# IO.net
KiCad netlist of a schematic drawn in Altium Designer
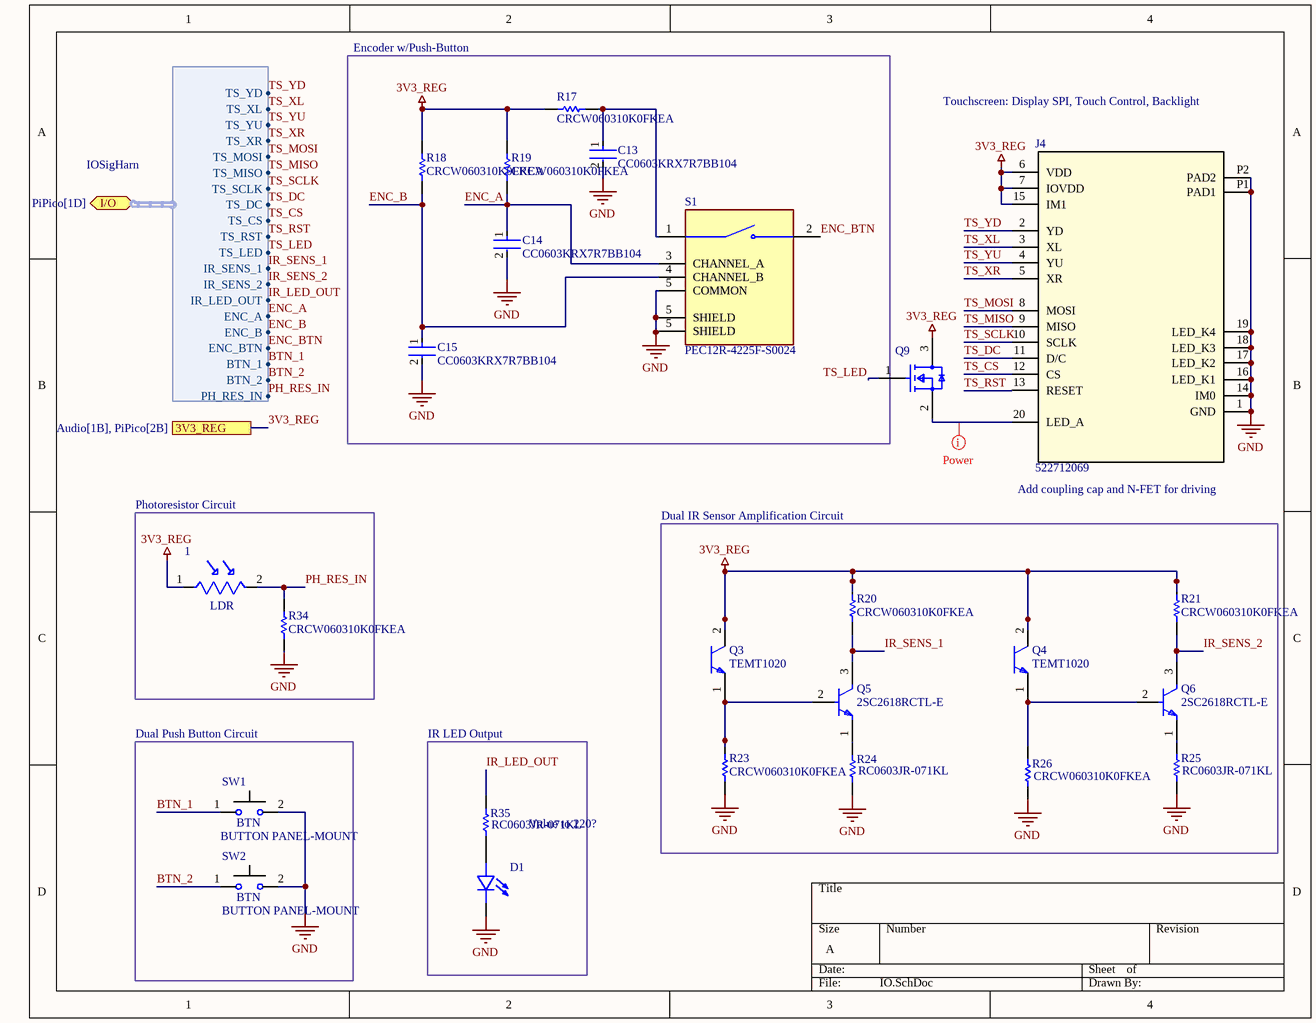
[diagram p0: IO.SchDoc]

(export (version "E")
  (design (tool "Eeschema 10.0.6"))
  (components
    (comp (ref "1")
      (value "LDR")
      (footprint "2-pin Header (Generic)")
      (description "Generic Photoresistor symbol for peripheral use.\r\nUses generic 2-Pin Header footprint.")
      (libsource (lib "ECE299_PCB") (part "PHOTORESISTOR GENERIC"))
    )
    (comp (ref "C13")
      (value "CC0603KRX7R7BB104")
      (footprint "FP-CC0603-DA-MFG")
      (description "CAP CER 0.1UF 16V X7R 0603")
      (fields
        (field (name "OCTOPART") "https://octopart.com/cc0603krx7r7bb104-yageo-192941")
        (field (name "TOLERANCE") "0.1")
      )
      (libsource (lib "Altium Content Vault") (part "11868f565c42a9108669ba33697ecf6"))
    )
    (comp (ref "C14")
      (value "CC0603KRX7R7BB104")
      (footprint "FP-CC0603-DA-MFG")
      (description "CAP CER 0.1UF 16V X7R 0603")
      (fields
        (field (name "OCTOPART") "https://octopart.com/cc0603krx7r7bb104-yageo-192941")
        (field (name "TOLERANCE") "0.1")
      )
      (libsource (lib "Altium Content Vault") (part "11868f565c42a9108669ba33697ecf6"))
    )
    (comp (ref "C15")
      (value "CC0603KRX7R7BB104")
      (footprint "FP-CC0603-DA-MFG")
      (description "CAP CER 0.1UF 16V X7R 0603")
      (fields
        (field (name "OCTOPART") "https://octopart.com/cc0603krx7r7bb104-yageo-192941")
        (field (name "TOLERANCE") "0.1")
      )
      (libsource (lib "Altium Content Vault") (part "11868f565c42a9108669ba33697ecf6"))
    )
    (comp (ref "D1")
      (value "~")
      (footprint "2-pin Header (Generic)")
      (description "IR_LED")
      (fields (field (name "MF") "{'manufacturer': u'Kingbright'}") (field (name "MP") "APT1608SF4C-PRV"))
      (libsource (lib "APT1608SF4C-PRV") (part "APT1608SF4C-PRV"))
    )
    (comp (ref "J4")
      (value "522712069")
      (footprint "CON_522712069_MOL")
      (libsource (lib "522712069") (part "522712069"))
    )
    (comp (ref "Q3")
      (value "TEMT1020")
      (footprint "FP-6_544-5325_01-4-MFG")
      (description "SENSOR PHOTO 880NM TOP VIEW 2SMD")
      (fields
        (field (name "OCTOPART") "https://octopart.com/temt1020-vishay-39666707")
        (field (name "MANUFACTURER") "Vishay Semiconductor Opto Division")
      )
      (libsource (lib "Altium Content Vault") (part "dcd88daa71cb945d3e90ade5296eb2f"))
    )
    (comp (ref "Q4")
      (value "TEMT1020")
      (footprint "FP-6_544-5325_01-4-MFG")
      (description "SENSOR PHOTO 880NM TOP VIEW 2SMD")
      (fields
        (field (name "OCTOPART") "https://octopart.com/temt1020-vishay-39666707")
        (field (name "MANUFACTURER") "Vishay Semiconductor Opto Division")
      )
      (libsource (lib "Altium Content Vault") (part "dcd88daa71cb945d3e90ade5296eb2f"))
    )
    (comp (ref "Q5")
      (value "2SC2618RCTL-E")
      (footprint "PLSP0003ZB-A_P213_MFG")
      (description "Trans Gp Bjt NPN 35V 0.5A 3-PIN Mpak T/r")
      (libsource (lib "Altium Content Vault") (part "66ef7c62b17c908413b088e63760a96"))
    )
    (comp (ref "Q6")
      (value "2SC2618RCTL-E")
      (footprint "PLSP0003ZB-A_P213_MFG")
      (description "Trans Gp Bjt NPN 35V 0.5A 3-PIN Mpak T/r")
      (libsource (lib "Altium Content Vault") (part "66ef7c62b17c908413b088e63760a96"))
    )
    (comp (ref "Q9")
      (value "2N7002H6327XTSA2")
      (footprint "FP-PG-SOT23-3-MFG")
      (description "MOSFET N-CH 60V 0.3A SOT23")
      (libsource (lib "Altium Content Vault") (part "2d979dc9c009d20783d0745ce0ba7b4"))
    )
    (comp (ref "R17")
      (value "CRCW060310K0FKEA")
      (footprint "RESC1609X50X30NL8T20")
      (description "Chip Resistor, 10 KOhm, +/- 1%, 100 mW, -55 to 155 degC, 0603 (1608 Metric), RoHS, Tape and Reel")
      (fields (field (name "MANUFACTURER") "Vishay Semiconductor"))
      (libsource (lib "Altium Content Vault") (part "RES-2"))
    )
    (comp (ref "R18")
      (value "CRCW060310K0FKEA")
      (footprint "RESC1609X50X30NL8T20")
      (description "Chip Resistor, 10 KOhm, +/- 1%, 100 mW, -55 to 155 degC, 0603 (1608 Metric), RoHS, Tape and Reel")
      (fields (field (name "MANUFACTURER") "Vishay Semiconductor"))
      (libsource (lib "Altium Content Vault") (part "RES-2"))
    )
    (comp (ref "R19")
      (value "CRCW060310K0FKEA")
      (footprint "RESC1609X50X30NL8T20")
      (description "Chip Resistor, 10 KOhm, +/- 1%, 100 mW, -55 to 155 degC, 0603 (1608 Metric), RoHS, Tape and Reel")
      (fields (field (name "MANUFACTURER") "Vishay Semiconductor"))
      (libsource (lib "Altium Content Vault") (part "RES-2"))
    )
    (comp (ref "R20")
      (value "CRCW060310K0FKEA")
      (footprint "RESC1609X50X30NL8T20")
      (description "Chip Resistor, 10 KOhm, +/- 1%, 100 mW, -55 to 155 degC, 0603 (1608 Metric), RoHS, Tape and Reel")
      (fields (field (name "MANUFACTURER") "Vishay Semiconductor"))
      (libsource (lib "Altium Content Vault") (part "RES-2"))
    )
    (comp (ref "R21")
      (value "CRCW060310K0FKEA")
      (footprint "RESC1609X50X30NL8T20")
      (description "Chip Resistor, 10 KOhm, +/- 1%, 100 mW, -55 to 155 degC, 0603 (1608 Metric), RoHS, Tape and Reel")
      (fields (field (name "MANUFACTURER") "Vishay Semiconductor"))
      (libsource (lib "Altium Content Vault") (part "RES-2"))
    )
    (comp (ref "R23")
      (value "CRCW060310K0FKEA")
      (footprint "RESC1609X50X30NL8T20")
      (description "Chip Resistor, 10 KOhm, +/- 1%, 100 mW, -55 to 155 degC, 0603 (1608 Metric), RoHS, Tape and Reel")
      (fields (field (name "MANUFACTURER") "Vishay Semiconductor"))
      (libsource (lib "Altium Content Vault") (part "RES-2"))
    )
    (comp (ref "R24")
      (value "RC0603JR-071KL")
      (footprint "RESC1608X55X25ML10T15")
      (description "Chip Resistor, 1 KOhm, +/- 5%, 0.063 W, -55 to 155 degC, 0603 (1608 Metric), RoHS, Tape and Reel")
      (fields (field (name "MANUFACTURER") "Yageo"))
      (libsource (lib "Altium Content Vault") (part "RES-2"))
    )
    (comp (ref "R25")
      (value "RC0603JR-071KL")
      (footprint "RESC1608X55X25ML10T15")
      (description "Chip Resistor, 1 KOhm, +/- 5%, 0.063 W, -55 to 155 degC, 0603 (1608 Metric), RoHS, Tape and Reel")
      (fields (field (name "MANUFACTURER") "Yageo"))
      (libsource (lib "Altium Content Vault") (part "RES-2"))
    )
    (comp (ref "R26")
      (value "CRCW060310K0FKEA")
      (footprint "RESC1609X50X30NL8T20")
      (description "Chip Resistor, 10 KOhm, +/- 1%, 100 mW, -55 to 155 degC, 0603 (1608 Metric), RoHS, Tape and Reel")
      (fields (field (name "MANUFACTURER") "Vishay Semiconductor"))
      (libsource (lib "Altium Content Vault") (part "RES-2"))
    )
    (comp (ref "R34")
      (value "CRCW060310K0FKEA")
      (footprint "RESC1609X50X30NL8T20")
      (description "Chip Resistor, 10 KOhm, +/- 1%, 100 mW, -55 to 155 degC, 0603 (1608 Metric), RoHS, Tape and Reel")
      (fields (field (name "MANUFACTURER") "Vishay Semiconductor"))
      (libsource (lib "Altium Content Vault") (part "RES-2"))
    )
    (comp (ref "R35")
      (value "RC0603JR-071KL")
      (footprint "RESC1608X55X25ML10T15")
      (description "Chip Resistor, 1 KOhm, +/- 5%, 0.063 W, -55 to 155 degC, 0603 (1608 Metric), RoHS, Tape and Reel")
      (fields (field (name "MANUFACTURER") "Yageo"))
      (libsource (lib "Altium Content Vault") (part "RES-2"))
    )
    (comp (ref "S1")
      (value "PEC12R-4225F-S0024")
      (footprint "5-pin Header (Generic)")
      (fields (field (name "MF") "Bourns"))
      (libsource (lib "PEC12R-4225F-S0024") (part "PEC12R-4225F-S0024"))
    )
    (comp (ref "SW1")
      (value "BUTTON PANEL-MOUNT")
      (footprint "2-pin Header (Generic)")
      (libsource (lib "ECE299_PCB") (part "BUTTON PANEL-MOUNT"))
    )
    (comp (ref "SW2")
      (value "BUTTON PANEL-MOUNT")
      (footprint "2-pin Header (Generic)")
      (libsource (lib "ECE299_PCB") (part "BUTTON PANEL-MOUNT"))
    )
  )
  (nets
    (net (code "2") (name "/BTN_1") (class "Default") (node (ref "SW1") (pin "1") (pintype "passive")))
    (net (code "3") (name "/BTN_2") (class "Default") (node (ref "SW2") (pin "1") (pintype "passive")))
    (net (code "4") (name "/ENC_A") (class "Default")
      (node (ref "C14") (pin "1") (pinfunction "1_1") (pintype "passive"))
      (node (ref "R19") (pin "1") (pinfunction "1_1") (pintype "passive"))
      (node (ref "S1") (pin "3") (pinfunction "CHANNEL_A_3") (pintype "passive"))
    )
    (net (code "5") (name "/ENC_B") (class "Default")
      (node (ref "C15") (pin "1") (pinfunction "1_1") (pintype "passive"))
      (node (ref "R18") (pin "1") (pinfunction "1_1") (pintype "passive"))
      (node (ref "S1") (pin "4") (pinfunction "CHANNEL_B_4") (pintype "passive"))
    )
    (net (code "6") (name "/ENC_BTN") (class "Default")
      (node (ref "S1") (pin "2") (pinfunction "2_2") (pintype "passive"))
    )
    (net (code "7") (name "/IR_LED_OUT") (class "Default")
      (node (ref "R35") (pin "2") (pinfunction "2_2") (pintype "passive"))
    )
    (net (code "8") (name "/IR_SENS_1") (class "Default")
      (node (ref "Q5") (pin "3") (pinfunction "COLLECTOR_3") (pintype "passive"))
      (node (ref "R20") (pin "1") (pinfunction "1_1") (pintype "passive"))
    )
    (net (code "9") (name "/IR_SENS_2") (class "Default")
      (node (ref "Q6") (pin "3") (pinfunction "COLLECTOR_3") (pintype "passive"))
      (node (ref "R21") (pin "1") (pinfunction "1_1") (pintype "passive"))
    )
    (net (code "10") (name "/PH_RES_IN") (class "Default")
      (node (ref "1") (pin "2") (pintype "passive"))
      (node (ref "R34") (pin "2") (pinfunction "2_2") (pintype "passive"))
    )
    (net (code "11") (name "/TS_CS") (class "Default")
      (node (ref "J4") (pin "12") (pinfunction "CS_12") (pintype "passive"))
    )
    (net (code "12") (name "/TS_DC") (class "Default")
      (node (ref "J4") (pin "11") (pinfunction "D/C_11") (pintype "passive"))
    )
    (net (code "13") (name "/TS_LED") (class "Default")
      (node (ref "Q9") (pin "1") (pinfunction "gate_1") (pintype "passive"))
    )
    (net (code "14") (name "/TS_MISO") (class "Default")
      (node (ref "J4") (pin "9") (pinfunction "MISO_9") (pintype "passive"))
    )
    (net (code "15") (name "/TS_MOSI") (class "Default")
      (node (ref "J4") (pin "8") (pinfunction "MOSI_8") (pintype "passive"))
    )
    (net (code "16") (name "/TS_RST") (class "Default")
      (node (ref "J4") (pin "13") (pinfunction "RESET_13") (pintype "passive"))
    )
    (net (code "17") (name "/TS_SCLK") (class "Default")
      (node (ref "J4") (pin "10") (pinfunction "SCLK_10") (pintype "passive"))
    )
    (net (code "18") (name "/TS_XL") (class "Default")
      (node (ref "J4") (pin "3") (pinfunction "XL_3") (pintype "passive"))
    )
    (net (code "19") (name "/TS_XR") (class "Default")
      (node (ref "J4") (pin "5") (pinfunction "XR_5") (pintype "passive"))
    )
    (net (code "20") (name "/TS_YD") (class "Default")
      (node (ref "J4") (pin "2") (pinfunction "YD_2") (pintype "passive"))
    )
    (net (code "21") (name "/TS_YU") (class "Default")
      (node (ref "J4") (pin "4") (pinfunction "YU_4") (pintype "passive"))
    )
    (net (code "23") (name "<NO NET>") (class "Default")
      (node (ref "1") (pin "1") (pintype "passive"))
      (node (ref "J4") (pin "15") (pinfunction "IM1_15") (pintype "passive"))
      (node (ref "J4") (pin "6") (pinfunction "VDD_6") (pintype "passive"))
      (node (ref "J4") (pin "7") (pinfunction "IOVDD_7") (pintype "passive"))
      (node (ref "Q3") (pin "2") (pinfunction "C_2") (pintype "passive"))
      (node (ref "Q4") (pin "2") (pinfunction "C_2") (pintype "passive"))
      (node (ref "Q9") (pin "3") (pinfunction "drain_3") (pintype "passive"))
      (node (ref "R17") (pin "2") (pinfunction "2_2") (pintype "passive"))
      (node (ref "R18") (pin "2") (pinfunction "2_2") (pintype "passive"))
      (node (ref "R19") (pin "2") (pinfunction "2_2") (pintype "passive"))
      (node (ref "R20") (pin "2") (pinfunction "2_2") (pintype "passive"))
      (node (ref "R21") (pin "2") (pinfunction "2_2") (pintype "passive"))
    )
    (net (code "24") (name "GND") (class "Default")
      (node (ref "C13") (pin "2") (pinfunction "2_2") (pintype "passive"))
      (node (ref "C14") (pin "2") (pinfunction "2_2") (pintype "passive"))
      (node (ref "C15") (pin "2") (pinfunction "2_2") (pintype "passive"))
      (node (ref "D1") (pin "1") (pinfunction "C_1") (pintype "passive"))
      (node (ref "J4") (pin "1") (pinfunction "GND_1") (pintype "passive"))
      (node (ref "J4") (pin "14") (pinfunction "IM0_14") (pintype "passive"))
      (node (ref "J4") (pin "16") (pinfunction "LED_K1_16") (pintype "passive"))
      (node (ref "J4") (pin "17") (pinfunction "LED_K2_17") (pintype "passive"))
      (node (ref "J4") (pin "18") (pinfunction "LED_K3_18") (pintype "passive"))
      (node (ref "J4") (pin "19") (pinfunction "LED_K4_19") (pintype "passive"))
      (node (ref "J4") (pin "P1") (pinfunction "PAD1_P1") (pintype "passive"))
      (node (ref "J4") (pin "P2") (pinfunction "PAD2_P2") (pintype "passive"))
      (node (ref "R23") (pin "1") (pinfunction "1_1") (pintype "passive"))
      (node (ref "R24") (pin "1") (pinfunction "1_1") (pintype "passive"))
      (node (ref "R25") (pin "1") (pinfunction "1_1") (pintype "passive"))
      (node (ref "R26") (pin "1") (pinfunction "1_1") (pintype "passive"))
      (node (ref "R34") (pin "1") (pinfunction "1_1") (pintype "passive"))
      (node (ref "S1") (pin "5") (pinfunction "COMMON_5") (pintype "passive"))
      (node (ref "SW1") (pin "2") (pintype "passive"))
      (node (ref "SW2") (pin "2") (pintype "passive"))
    )
    (net (code "25") (name "Net-(C13-Pad1)") (class "Default")
      (node (ref "C13") (pin "1") (pinfunction "1_1") (pintype "passive"))
      (node (ref "R17") (pin "1") (pinfunction "1_1") (pintype "passive"))
      (node (ref "S1") (pin "1") (pinfunction "1_1") (pintype "passive"))
    )
    (net (code "26") (name "Net-(D1-A)") (class "Default")
      (node (ref "D1") (pin "2") (pinfunction "A_2") (pintype "passive"))
      (node (ref "R35") (pin "1") (pinfunction "1_1") (pintype "passive"))
    )
    (net (code "27") (name "Net-(J4-LED_A)") (class "Default")
      (node (ref "J4") (pin "20") (pinfunction "LED_A_20") (pintype "passive"))
      (node (ref "Q9") (pin "2") (pinfunction "source_2") (pintype "passive"))
    )
    (net (code "28") (name "Net-(Q3-E)") (class "Default")
      (node (ref "Q3") (pin "1") (pinfunction "E_1") (pintype "passive"))
      (node (ref "Q5") (pin "2") (pinfunction "BASE_2") (pintype "passive"))
      (node (ref "R23") (pin "2") (pinfunction "2_2") (pintype "passive"))
    )
    (net (code "29") (name "Net-(Q4-E)") (class "Default")
      (node (ref "Q4") (pin "1") (pinfunction "E_1") (pintype "passive"))
      (node (ref "Q6") (pin "2") (pinfunction "BASE_2") (pintype "passive"))
      (node (ref "R26") (pin "2") (pinfunction "2_2") (pintype "passive"))
    )
    (net (code "30") (name "Net-(Q5-EMITTER)") (class "Default")
      (node (ref "Q5") (pin "1") (pinfunction "EMITTER_1") (pintype "passive"))
      (node (ref "R24") (pin "2") (pinfunction "2_2") (pintype "passive"))
    )
    (net (code "31") (name "Net-(Q6-EMITTER)") (class "Default")
      (node (ref "Q6") (pin "1") (pinfunction "EMITTER_1") (pintype "passive"))
      (node (ref "R25") (pin "2") (pinfunction "2_2") (pintype "passive"))
    )
  )
)
